# WifiDriver.net
KiCad netlist of a schematic drawn in EAGLE
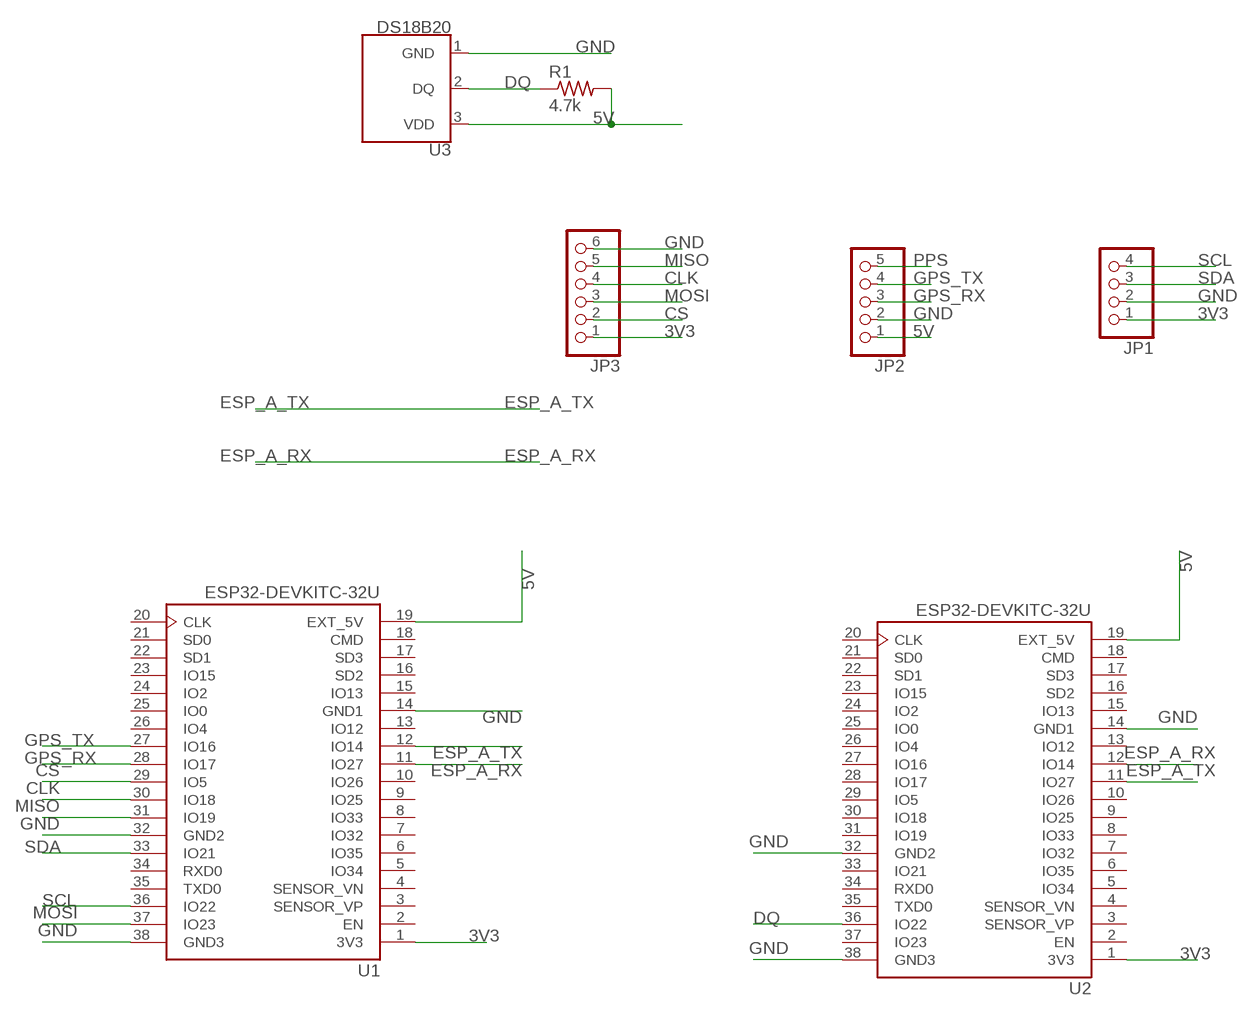
[diagram p0: schematic, sheet 1]

(export (version "E")
  (design (tool "Eeschema 10.0.6"))
  (components
    (comp (ref "JP1")
      (value "PINHD-1X4")
      (footprint "eagle-import:1X04")
      (libsource (lib "eagle-import") (part "PINHD-1X4"))
    )
    (comp (ref "JP2")
      (value "PINHD-1X5")
      (footprint "eagle-import:1X05")
      (libsource (lib "eagle-import") (part "PINHD-1X5"))
    )
    (comp (ref "JP3")
      (value "PINHD-1X6")
      (footprint "eagle-import:1X06")
      (libsource (lib "eagle-import") (part "PINHD-1X6"))
    )
    (comp (ref "R1")
      (value "4.7k")
      (footprint "eagle-import:0805-THM")
      (libsource (lib "eagle-import") (part "FLIPFLOP-RES"))
    )
    (comp (ref "U1")
      (value "ESP32-DEVKITC-32U")
      (footprint "eagle-import:MODULE_ESP32-DEVKITC-32U")
      (fields (field (name "MF") "Espressif Systems"))
      (libsource (lib "eagle-import") (part "ESP32-DEVKITC-32U"))
    )
    (comp (ref "U2")
      (value "ESP32-DEVKITC-32U")
      (footprint "eagle-import:MODULE_ESP32-DEVKITC-32U")
      (fields (field (name "MF") "Espressif Systems"))
      (libsource (lib "eagle-import") (part "ESP32-DEVKITC-32U"))
    )
    (comp (ref "U3")
      (value "DS18B20")
      (footprint "eagle-import:TO-92-AMMO")
      (libsource (lib "eagle-import") (part "DS18B20"))
    )
  )
  (nets
    (net (code "1") (name "/3V3") (class "Default")
      (node (ref "JP1") (pin "1") (pinfunction "1_1") (pintype "passive"))
      (node (ref "JP3") (pin "1") (pinfunction "1_1") (pintype "passive"))
      (node (ref "U1") (pin "1") (pinfunction "3V3_1") (pintype "power_in"))
      (node (ref "U2") (pin "1") (pinfunction "3V3_1") (pintype "power_in"))
    )
    (net (code "2") (name "/5V") (class "Default")
      (node (ref "JP2") (pin "1") (pinfunction "1_1") (pintype "passive"))
      (node (ref "R1") (pin "2") (pinfunction "2_2") (pintype "passive"))
      (node (ref "U1") (pin "19") (pinfunction "EXT_5V_19") (pintype "power_in"))
      (node (ref "U2") (pin "19") (pinfunction "EXT_5V_19") (pintype "power_in"))
      (node (ref "U3") (pin "3") (pinfunction "VDD_3") (pintype "power_in"))
    )
    (net (code "3") (name "/CLK") (class "Default")
      (node (ref "JP3") (pin "4") (pinfunction "4_4") (pintype "passive"))
      (node (ref "U1") (pin "30") (pinfunction "IO18_30") (pintype "bidirectional"))
    )
    (net (code "4") (name "/CS") (class "Default")
      (node (ref "JP3") (pin "2") (pinfunction "2_2") (pintype "passive"))
      (node (ref "U1") (pin "29") (pinfunction "IO5_29") (pintype "bidirectional"))
    )
    (net (code "5") (name "/DQ") (class "Default")
      (node (ref "R1") (pin "1") (pinfunction "1_1") (pintype "passive"))
      (node (ref "U2") (pin "36") (pinfunction "IO22_36") (pintype "bidirectional"))
      (node (ref "U3") (pin "2") (pinfunction "DQ_2") (pintype "bidirectional"))
    )
    (net (code "6") (name "/ESP_A_RX") (class "Default")
      (node (ref "U1") (pin "11") (pinfunction "IO27_11") (pintype "bidirectional"))
      (node (ref "U2") (pin "12") (pinfunction "IO14_12") (pintype "bidirectional"))
    )
    (net (code "7") (name "/ESP_A_TX") (class "Default")
      (node (ref "U1") (pin "12") (pinfunction "IO14_12") (pintype "bidirectional"))
      (node (ref "U2") (pin "11") (pinfunction "IO27_11") (pintype "bidirectional"))
    )
    (net (code "8") (name "/GND") (class "Default")
      (node (ref "JP1") (pin "2") (pinfunction "2_2") (pintype "passive"))
      (node (ref "JP2") (pin "2") (pinfunction "2_2") (pintype "passive"))
      (node (ref "JP3") (pin "6") (pinfunction "6_6") (pintype "passive"))
      (node (ref "U1") (pin "14") (pinfunction "GND1_14") (pintype "power_in"))
      (node (ref "U1") (pin "32") (pinfunction "GND2_32") (pintype "power_in"))
      (node (ref "U1") (pin "38") (pinfunction "GND3_38") (pintype "power_in"))
      (node (ref "U2") (pin "14") (pinfunction "GND1_14") (pintype "power_in"))
      (node (ref "U2") (pin "32") (pinfunction "GND2_32") (pintype "power_in"))
      (node (ref "U2") (pin "38") (pinfunction "GND3_38") (pintype "power_in"))
      (node (ref "U3") (pin "1") (pinfunction "GND_1") (pintype "power_in"))
    )
    (net (code "9") (name "/GPS_RX") (class "Default")
      (node (ref "JP2") (pin "3") (pinfunction "3_3") (pintype "passive"))
      (node (ref "U1") (pin "28") (pinfunction "IO17_28") (pintype "bidirectional"))
    )
    (net (code "10") (name "/GPS_TX") (class "Default")
      (node (ref "JP2") (pin "4") (pinfunction "4_4") (pintype "passive"))
      (node (ref "U1") (pin "27") (pinfunction "IO16_27") (pintype "bidirectional"))
    )
    (net (code "11") (name "/MISO") (class "Default")
      (node (ref "JP3") (pin "5") (pinfunction "5_5") (pintype "passive"))
      (node (ref "U1") (pin "31") (pinfunction "IO19_31") (pintype "bidirectional"))
    )
    (net (code "12") (name "/MOSI") (class "Default")
      (node (ref "JP3") (pin "3") (pinfunction "3_3") (pintype "passive"))
      (node (ref "U1") (pin "37") (pinfunction "IO23_37") (pintype "bidirectional"))
    )
    (net (code "13") (name "/PPS") (class "Default")
      (node (ref "JP2") (pin "5") (pinfunction "5_5") (pintype "passive"))
    )
    (net (code "14") (name "/SCL") (class "Default")
      (node (ref "JP1") (pin "4") (pinfunction "4_4") (pintype "passive"))
      (node (ref "U1") (pin "36") (pinfunction "IO22_36") (pintype "bidirectional"))
    )
    (net (code "15") (name "/SDA") (class "Default")
      (node (ref "JP1") (pin "3") (pinfunction "3_3") (pintype "passive"))
      (node (ref "U1") (pin "33") (pinfunction "IO21_33") (pintype "bidirectional"))
    )
    (net (code "16") (name "unconnected-(U1-CLK-Pad20)") (class "Default")
      (node (ref "U1") (pin "20") (pinfunction "CLK_20") (pintype "input"))
    )
    (net (code "17") (name "unconnected-(U1-CMD-Pad18)") (class "Default")
      (node (ref "U1") (pin "18") (pinfunction "CMD_18") (pintype "bidirectional"))
    )
    (net (code "18") (name "unconnected-(U1-EN-Pad2)") (class "Default")
      (node (ref "U1") (pin "2") (pinfunction "EN_2") (pintype "input"))
    )
    (net (code "19") (name "unconnected-(U1-IO0-Pad25)") (class "Default")
      (node (ref "U1") (pin "25") (pinfunction "IO0_25") (pintype "bidirectional"))
    )
    (net (code "20") (name "unconnected-(U1-IO2-Pad24)") (class "Default")
      (node (ref "U1") (pin "24") (pinfunction "IO2_24") (pintype "bidirectional"))
    )
    (net (code "21") (name "unconnected-(U1-IO4-Pad26)") (class "Default")
      (node (ref "U1") (pin "26") (pinfunction "IO4_26") (pintype "bidirectional"))
    )
    (net (code "22") (name "unconnected-(U1-IO12-Pad13)") (class "Default")
      (node (ref "U1") (pin "13") (pinfunction "IO12_13") (pintype "bidirectional"))
    )
    (net (code "23") (name "unconnected-(U1-IO13-Pad15)") (class "Default")
      (node (ref "U1") (pin "15") (pinfunction "IO13_15") (pintype "bidirectional"))
    )
    (net (code "24") (name "unconnected-(U1-IO15-Pad23)") (class "Default")
      (node (ref "U1") (pin "23") (pinfunction "IO15_23") (pintype "bidirectional"))
    )
    (net (code "25") (name "unconnected-(U1-IO25-Pad9)") (class "Default")
      (node (ref "U1") (pin "9") (pinfunction "IO25_9") (pintype "bidirectional"))
    )
    (net (code "26") (name "unconnected-(U1-IO26-Pad10)") (class "Default")
      (node (ref "U1") (pin "10") (pinfunction "IO26_10") (pintype "bidirectional"))
    )
    (net (code "27") (name "unconnected-(U1-IO32-Pad7)") (class "Default")
      (node (ref "U1") (pin "7") (pinfunction "IO32_7") (pintype "bidirectional"))
    )
    (net (code "28") (name "unconnected-(U1-IO33-Pad8)") (class "Default")
      (node (ref "U1") (pin "8") (pinfunction "IO33_8") (pintype "bidirectional"))
    )
    (net (code "29") (name "unconnected-(U1-IO34-Pad5)") (class "Default")
      (node (ref "U1") (pin "5") (pinfunction "IO34_5") (pintype "bidirectional"))
    )
    (net (code "30") (name "unconnected-(U1-IO35-Pad6)") (class "Default")
      (node (ref "U1") (pin "6") (pinfunction "IO35_6") (pintype "bidirectional"))
    )
    (net (code "31") (name "unconnected-(U1-RXD0-Pad34)") (class "Default")
      (node (ref "U1") (pin "34") (pinfunction "RXD0_34") (pintype "input"))
    )
    (net (code "32") (name "unconnected-(U1-SD0-Pad21)") (class "Default")
      (node (ref "U1") (pin "21") (pinfunction "SD0_21") (pintype "bidirectional"))
    )
    (net (code "33") (name "unconnected-(U1-SD1-Pad22)") (class "Default")
      (node (ref "U1") (pin "22") (pinfunction "SD1_22") (pintype "bidirectional"))
    )
    (net (code "34") (name "unconnected-(U1-SD2-Pad16)") (class "Default")
      (node (ref "U1") (pin "16") (pinfunction "SD2_16") (pintype "bidirectional"))
    )
    (net (code "35") (name "unconnected-(U1-SD3-Pad17)") (class "Default")
      (node (ref "U1") (pin "17") (pinfunction "SD3_17") (pintype "bidirectional"))
    )
    (net (code "36") (name "unconnected-(U1-SENSOR_VN-Pad4)") (class "Default")
      (node (ref "U1") (pin "4") (pinfunction "SENSOR_VN_4") (pintype "input"))
    )
    (net (code "37") (name "unconnected-(U1-SENSOR_VP-Pad3)") (class "Default")
      (node (ref "U1") (pin "3") (pinfunction "SENSOR_VP_3") (pintype "input"))
    )
    (net (code "38") (name "unconnected-(U1-TXD0-Pad35)") (class "Default")
      (node (ref "U1") (pin "35") (pinfunction "TXD0_35") (pintype "output"))
    )
    (net (code "39") (name "unconnected-(U2-CLK-Pad20)") (class "Default")
      (node (ref "U2") (pin "20") (pinfunction "CLK_20") (pintype "input"))
    )
    (net (code "40") (name "unconnected-(U2-CMD-Pad18)") (class "Default")
      (node (ref "U2") (pin "18") (pinfunction "CMD_18") (pintype "bidirectional"))
    )
    (net (code "41") (name "unconnected-(U2-EN-Pad2)") (class "Default")
      (node (ref "U2") (pin "2") (pinfunction "EN_2") (pintype "input"))
    )
    (net (code "42") (name "unconnected-(U2-IO0-Pad25)") (class "Default")
      (node (ref "U2") (pin "25") (pinfunction "IO0_25") (pintype "bidirectional"))
    )
    (net (code "43") (name "unconnected-(U2-IO2-Pad24)") (class "Default")
      (node (ref "U2") (pin "24") (pinfunction "IO2_24") (pintype "bidirectional"))
    )
    (net (code "44") (name "unconnected-(U2-IO4-Pad26)") (class "Default")
      (node (ref "U2") (pin "26") (pinfunction "IO4_26") (pintype "bidirectional"))
    )
    (net (code "45") (name "unconnected-(U2-IO5-Pad29)") (class "Default")
      (node (ref "U2") (pin "29") (pinfunction "IO5_29") (pintype "bidirectional"))
    )
    (net (code "46") (name "unconnected-(U2-IO12-Pad13)") (class "Default")
      (node (ref "U2") (pin "13") (pinfunction "IO12_13") (pintype "bidirectional"))
    )
    (net (code "47") (name "unconnected-(U2-IO13-Pad15)") (class "Default")
      (node (ref "U2") (pin "15") (pinfunction "IO13_15") (pintype "bidirectional"))
    )
    (net (code "48") (name "unconnected-(U2-IO15-Pad23)") (class "Default")
      (node (ref "U2") (pin "23") (pinfunction "IO15_23") (pintype "bidirectional"))
    )
    (net (code "49") (name "unconnected-(U2-IO16-Pad27)") (class "Default")
      (node (ref "U2") (pin "27") (pinfunction "IO16_27") (pintype "bidirectional"))
    )
    (net (code "50") (name "unconnected-(U2-IO17-Pad28)") (class "Default")
      (node (ref "U2") (pin "28") (pinfunction "IO17_28") (pintype "bidirectional"))
    )
    (net (code "51") (name "unconnected-(U2-IO18-Pad30)") (class "Default")
      (node (ref "U2") (pin "30") (pinfunction "IO18_30") (pintype "bidirectional"))
    )
    (net (code "52") (name "unconnected-(U2-IO19-Pad31)") (class "Default")
      (node (ref "U2") (pin "31") (pinfunction "IO19_31") (pintype "bidirectional"))
    )
    (net (code "53") (name "unconnected-(U2-IO21-Pad33)") (class "Default")
      (node (ref "U2") (pin "33") (pinfunction "IO21_33") (pintype "bidirectional"))
    )
    (net (code "54") (name "unconnected-(U2-IO23-Pad37)") (class "Default")
      (node (ref "U2") (pin "37") (pinfunction "IO23_37") (pintype "bidirectional"))
    )
    (net (code "55") (name "unconnected-(U2-IO25-Pad9)") (class "Default")
      (node (ref "U2") (pin "9") (pinfunction "IO25_9") (pintype "bidirectional"))
    )
    (net (code "56") (name "unconnected-(U2-IO26-Pad10)") (class "Default")
      (node (ref "U2") (pin "10") (pinfunction "IO26_10") (pintype "bidirectional"))
    )
    (net (code "57") (name "unconnected-(U2-IO32-Pad7)") (class "Default")
      (node (ref "U2") (pin "7") (pinfunction "IO32_7") (pintype "bidirectional"))
    )
    (net (code "58") (name "unconnected-(U2-IO33-Pad8)") (class "Default")
      (node (ref "U2") (pin "8") (pinfunction "IO33_8") (pintype "bidirectional"))
    )
    (net (code "59") (name "unconnected-(U2-IO34-Pad5)") (class "Default")
      (node (ref "U2") (pin "5") (pinfunction "IO34_5") (pintype "bidirectional"))
    )
    (net (code "60") (name "unconnected-(U2-IO35-Pad6)") (class "Default")
      (node (ref "U2") (pin "6") (pinfunction "IO35_6") (pintype "bidirectional"))
    )
    (net (code "61") (name "unconnected-(U2-RXD0-Pad34)") (class "Default")
      (node (ref "U2") (pin "34") (pinfunction "RXD0_34") (pintype "input"))
    )
    (net (code "62") (name "unconnected-(U2-SD0-Pad21)") (class "Default")
      (node (ref "U2") (pin "21") (pinfunction "SD0_21") (pintype "bidirectional"))
    )
    (net (code "63") (name "unconnected-(U2-SD1-Pad22)") (class "Default")
      (node (ref "U2") (pin "22") (pinfunction "SD1_22") (pintype "bidirectional"))
    )
    (net (code "64") (name "unconnected-(U2-SD2-Pad16)") (class "Default")
      (node (ref "U2") (pin "16") (pinfunction "SD2_16") (pintype "bidirectional"))
    )
    (net (code "65") (name "unconnected-(U2-SD3-Pad17)") (class "Default")
      (node (ref "U2") (pin "17") (pinfunction "SD3_17") (pintype "bidirectional"))
    )
    (net (code "66") (name "unconnected-(U2-SENSOR_VN-Pad4)") (class "Default")
      (node (ref "U2") (pin "4") (pinfunction "SENSOR_VN_4") (pintype "input"))
    )
    (net (code "67") (name "unconnected-(U2-SENSOR_VP-Pad3)") (class "Default")
      (node (ref "U2") (pin "3") (pinfunction "SENSOR_VP_3") (pintype "input"))
    )
    (net (code "68") (name "unconnected-(U2-TXD0-Pad35)") (class "Default")
      (node (ref "U2") (pin "35") (pinfunction "TXD0_35") (pintype "output"))
    )
  )
)
